# design.net
KiCad netlist of a schematic drawn in Altium Designer
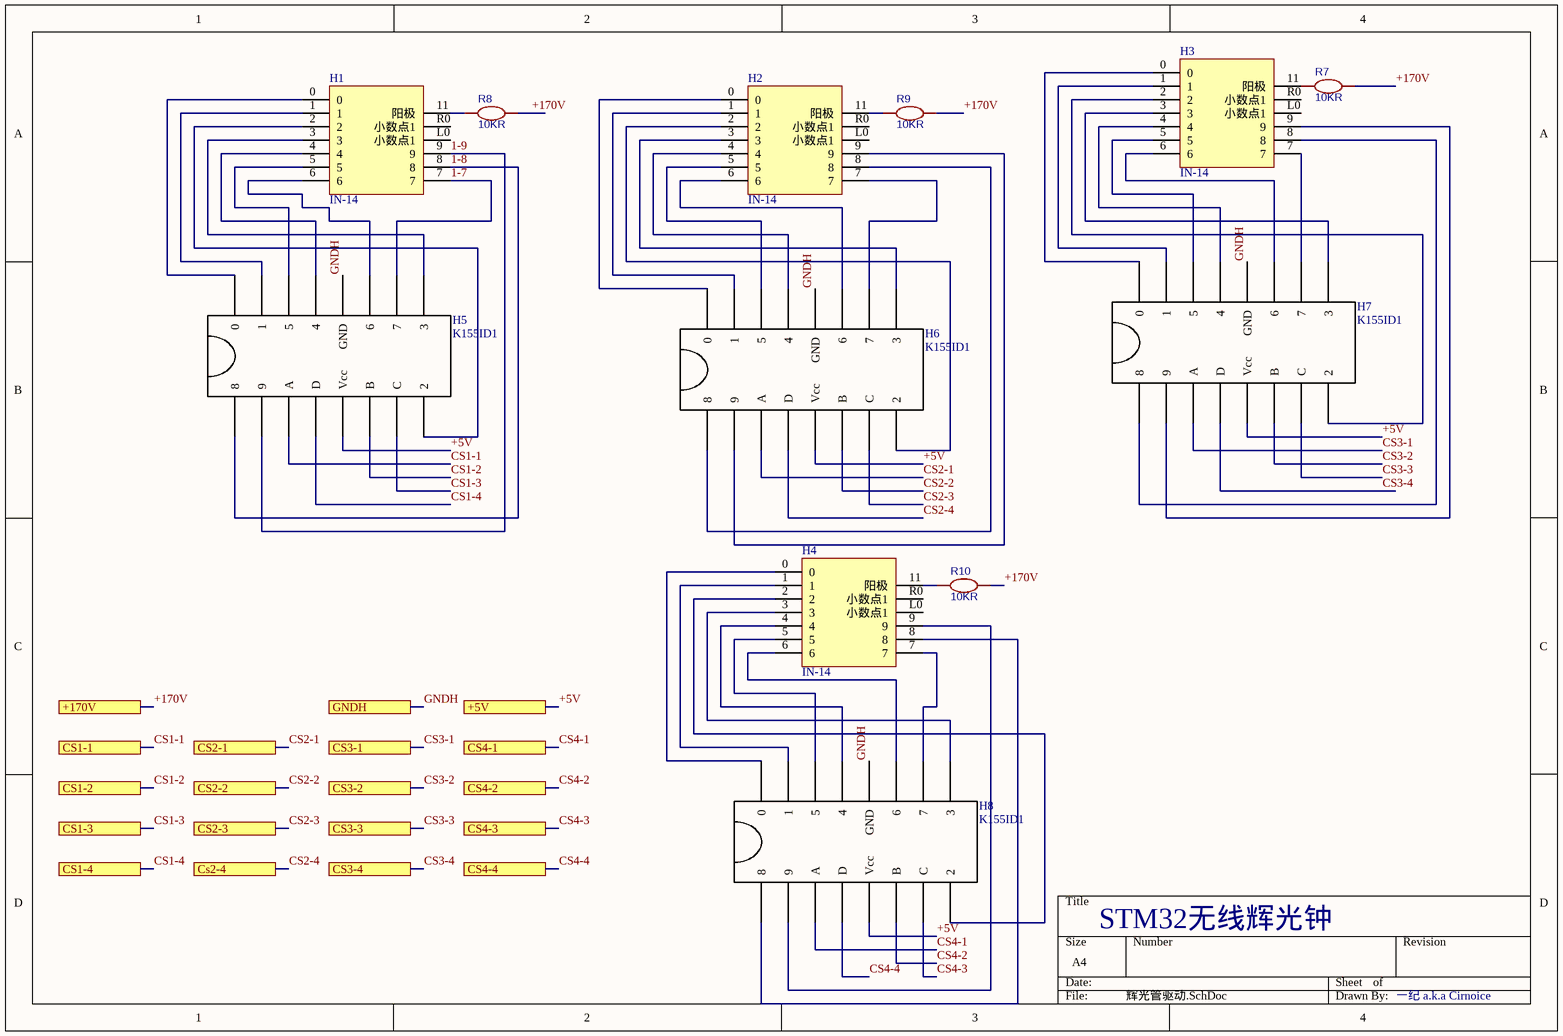
[diagram p0: 辉光管驱动.SchDoc]

(export (version "E")
  (design (tool "Eeschema 10.0.6"))
  (components
    (comp (ref "H1") (value "IN-14") (footprint "IN-14") (libsource (lib "Nixie_ESP32") (part "IN-14")))
    (comp (ref "H2") (value "IN-14") (footprint "IN-14") (libsource (lib "Nixie_ESP32") (part "IN-14")))
    (comp (ref "H3") (value "IN-14") (footprint "IN-14") (libsource (lib "Nixie_ESP32") (part "IN-14")))
    (comp (ref "H4") (value "IN-14") (footprint "IN-14") (libsource (lib "Nixie_ESP32") (part "IN-14")))
    (comp (ref "H5") (value "K155ID1") (footprint "DIP-16") (libsource (lib "Nixie_ESP32") (part "K155ID1")))
    (comp (ref "H6") (value "K155ID1") (footprint "DIP-16") (libsource (lib "Nixie_ESP32") (part "K155ID1")))
    (comp (ref "H7") (value "K155ID1") (footprint "DIP-16") (libsource (lib "Nixie_ESP32") (part "K155ID1")))
    (comp (ref "H8") (value "K155ID1") (footprint "DIP-16") (libsource (lib "Nixie_ESP32") (part "K155ID1")))
    (comp (ref "R7")
      (value "10KR")
      (footprint "R0603")
      (fields (field (name "CONTRIBUTOR") "LCEDA_Lib"))
      (libsource (lib "Nixie_ESP32") (part "0603R"))
    )
    (comp (ref "R8")
      (value "10KR")
      (footprint "R0603")
      (fields (field (name "CONTRIBUTOR") "LCEDA_Lib"))
      (libsource (lib "Nixie_ESP32") (part "0603R"))
    )
    (comp (ref "R9")
      (value "10KR")
      (footprint "R0603")
      (fields (field (name "CONTRIBUTOR") "LCEDA_Lib"))
      (libsource (lib "Nixie_ESP32") (part "0603R"))
    )
    (comp (ref "R10")
      (value "10KR")
      (footprint "R0603")
      (fields (field (name "CONTRIBUTOR") "LCEDA_Lib"))
      (libsource (lib "Nixie_ESP32") (part "0603R"))
    )
  )
  (nets
    (net (code "1") (name "/+5V") (class "Default")
      (node (ref "H5") (pin "5") (pinfunction "Vcc_5") (pintype "passive"))
      (node (ref "H6") (pin "5") (pinfunction "Vcc_5") (pintype "passive"))
      (node (ref "H7") (pin "5") (pinfunction "Vcc_5") (pintype "passive"))
      (node (ref "H8") (pin "5") (pinfunction "Vcc_5") (pintype "passive"))
    )
    (net (code "2") (name "/+170V") (class "Default")
      (node (ref "R10") (pin "2") (pinfunction "2_2") (pintype "passive"))
      (node (ref "R7") (pin "2") (pinfunction "2_2") (pintype "passive"))
      (node (ref "R8") (pin "2") (pinfunction "2_2") (pintype "passive"))
      (node (ref "R9") (pin "2") (pinfunction "2_2") (pintype "passive"))
    )
    (net (code "3") (name "/1-7") (class "Default")
      (node (ref "H1") (pin "7") (pinfunction "7_7") (pintype "passive"))
      (node (ref "H5") (pin "10") (pinfunction "7_10") (pintype "passive"))
    )
    (net (code "4") (name "/1-8") (class "Default")
      (node (ref "H1") (pin "8") (pinfunction "8_8") (pintype "passive"))
      (node (ref "H5") (pin "1") (pinfunction "8_1") (pintype "passive"))
    )
    (net (code "5") (name "/1-9") (class "Default")
      (node (ref "H1") (pin "9") (pinfunction "9_9") (pintype "passive"))
      (node (ref "H5") (pin "2") (pinfunction "9_2") (pintype "passive"))
    )
    (net (code "6") (name "/CS1-1") (class "Default")
      (node (ref "H5") (pin "3") (pinfunction "A_3") (pintype "passive"))
    )
    (net (code "7") (name "/CS1-2") (class "Default")
      (node (ref "H5") (pin "6") (pinfunction "B_6") (pintype "passive"))
    )
    (net (code "8") (name "/CS1-3") (class "Default")
      (node (ref "H5") (pin "7") (pinfunction "C_7") (pintype "passive"))
    )
    (net (code "9") (name "/CS1-4") (class "Default")
      (node (ref "H5") (pin "4") (pinfunction "D_4") (pintype "passive"))
    )
    (net (code "10") (name "/CS2-1") (class "Default")
      (node (ref "H6") (pin "3") (pinfunction "A_3") (pintype "passive"))
    )
    (net (code "11") (name "/CS2-2") (class "Default")
      (node (ref "H6") (pin "6") (pinfunction "B_6") (pintype "passive"))
    )
    (net (code "12") (name "/CS2-3") (class "Default")
      (node (ref "H6") (pin "7") (pinfunction "C_7") (pintype "passive"))
    )
    (net (code "13") (name "/CS2-4") (class "Default")
      (node (ref "H6") (pin "4") (pinfunction "D_4") (pintype "passive"))
    )
    (net (code "14") (name "/CS3-1") (class "Default")
      (node (ref "H7") (pin "3") (pinfunction "A_3") (pintype "passive"))
    )
    (net (code "15") (name "/CS3-2") (class "Default")
      (node (ref "H7") (pin "6") (pinfunction "B_6") (pintype "passive"))
    )
    (net (code "16") (name "/CS3-3") (class "Default")
      (node (ref "H7") (pin "7") (pinfunction "C_7") (pintype "passive"))
    )
    (net (code "17") (name "/CS3-4") (class "Default")
      (node (ref "H7") (pin "4") (pinfunction "D_4") (pintype "passive"))
    )
    (net (code "18") (name "/CS4-1") (class "Default")
      (node (ref "H8") (pin "3") (pinfunction "A_3") (pintype "passive"))
    )
    (net (code "19") (name "/CS4-2") (class "Default")
      (node (ref "H8") (pin "6") (pinfunction "B_6") (pintype "passive"))
    )
    (net (code "20") (name "/CS4-3") (class "Default")
      (node (ref "H8") (pin "7") (pinfunction "C_7") (pintype "passive"))
    )
    (net (code "21") (name "/CS4-4") (class "Default")
      (node (ref "H8") (pin "4") (pinfunction "D_4") (pintype "passive"))
    )
    (net (code "22") (name "/GNDH") (class "Default")
      (node (ref "H5") (pin "12") (pinfunction "GND_12") (pintype "passive"))
      (node (ref "H6") (pin "12") (pinfunction "GND_12") (pintype "passive"))
      (node (ref "H7") (pin "12") (pinfunction "GND_12") (pintype "passive"))
      (node (ref "H8") (pin "12") (pinfunction "GND_12") (pintype "passive"))
    )
    (net (code "23") (name "Net-(H1-阳极)") (class "Default")
      (node (ref "H1") (pin "11") (pinfunction "阳极_11") (pintype "passive"))
      (node (ref "R8") (pin "1") (pinfunction "1_1") (pintype "passive"))
    )
    (net (code "24") (name "Net-(H2-阳极)") (class "Default")
      (node (ref "H2") (pin "11") (pinfunction "阳极_11") (pintype "passive"))
      (node (ref "R9") (pin "1") (pinfunction "1_1") (pintype "passive"))
    )
    (net (code "25") (name "Net-(H3-阳极)") (class "Default")
      (node (ref "H3") (pin "11") (pinfunction "阳极_11") (pintype "passive"))
      (node (ref "R7") (pin "1") (pinfunction "1_1") (pintype "passive"))
    )
    (net (code "26") (name "Net-(H4-阳极)") (class "Default")
      (node (ref "H4") (pin "11") (pinfunction "阳极_11") (pintype "passive"))
      (node (ref "R10") (pin "1") (pinfunction "1_1") (pintype "passive"))
    )
    (net (code "27") (name "Net-(H5-0)") (class "Default")
      (node (ref "H1") (pin "0") (pinfunction "0_0") (pintype "passive"))
      (node (ref "H5") (pin "16") (pinfunction "0_16") (pintype "passive"))
    )
    (net (code "28") (name "Net-(H5-1)") (class "Default")
      (node (ref "H1") (pin "1") (pinfunction "1_1") (pintype "passive"))
      (node (ref "H5") (pin "15") (pinfunction "1_15") (pintype "passive"))
    )
    (net (code "29") (name "Net-(H5-2)") (class "Default")
      (node (ref "H1") (pin "2") (pinfunction "2_2") (pintype "passive"))
      (node (ref "H5") (pin "8") (pinfunction "2_8") (pintype "passive"))
    )
    (net (code "30") (name "Net-(H5-3)") (class "Default")
      (node (ref "H1") (pin "3") (pinfunction "3_3") (pintype "passive"))
      (node (ref "H5") (pin "9") (pinfunction "3_9") (pintype "passive"))
    )
    (net (code "31") (name "Net-(H5-4)") (class "Default")
      (node (ref "H1") (pin "4") (pinfunction "4_4") (pintype "passive"))
      (node (ref "H5") (pin "13") (pinfunction "4_13") (pintype "passive"))
    )
    (net (code "32") (name "Net-(H5-5)") (class "Default")
      (node (ref "H1") (pin "5") (pinfunction "5_5") (pintype "passive"))
      (node (ref "H5") (pin "14") (pinfunction "5_14") (pintype "passive"))
    )
    (net (code "33") (name "Net-(H5-6)") (class "Default")
      (node (ref "H1") (pin "6") (pinfunction "6_6") (pintype "passive"))
      (node (ref "H5") (pin "11") (pinfunction "6_11") (pintype "passive"))
    )
    (net (code "34") (name "Net-(H6-0)") (class "Default")
      (node (ref "H2") (pin "0") (pinfunction "0_0") (pintype "passive"))
      (node (ref "H6") (pin "16") (pinfunction "0_16") (pintype "passive"))
    )
    (net (code "35") (name "Net-(H6-1)") (class "Default")
      (node (ref "H2") (pin "1") (pinfunction "1_1") (pintype "passive"))
      (node (ref "H6") (pin "15") (pinfunction "1_15") (pintype "passive"))
    )
    (net (code "36") (name "Net-(H6-2)") (class "Default")
      (node (ref "H2") (pin "2") (pinfunction "2_2") (pintype "passive"))
      (node (ref "H6") (pin "8") (pinfunction "2_8") (pintype "passive"))
    )
    (net (code "37") (name "Net-(H6-3)") (class "Default")
      (node (ref "H2") (pin "3") (pinfunction "3_3") (pintype "passive"))
      (node (ref "H6") (pin "9") (pinfunction "3_9") (pintype "passive"))
    )
    (net (code "38") (name "Net-(H6-4)") (class "Default")
      (node (ref "H2") (pin "4") (pinfunction "4_4") (pintype "passive"))
      (node (ref "H6") (pin "13") (pinfunction "4_13") (pintype "passive"))
    )
    (net (code "39") (name "Net-(H6-5)") (class "Default")
      (node (ref "H2") (pin "5") (pinfunction "5_5") (pintype "passive"))
      (node (ref "H6") (pin "14") (pinfunction "5_14") (pintype "passive"))
    )
    (net (code "40") (name "Net-(H6-6)") (class "Default")
      (node (ref "H2") (pin "6") (pinfunction "6_6") (pintype "passive"))
      (node (ref "H6") (pin "11") (pinfunction "6_11") (pintype "passive"))
    )
    (net (code "41") (name "Net-(H6-7)") (class "Default")
      (node (ref "H2") (pin "7") (pinfunction "7_7") (pintype "passive"))
      (node (ref "H6") (pin "10") (pinfunction "7_10") (pintype "passive"))
    )
    (net (code "42") (name "Net-(H6-8)") (class "Default")
      (node (ref "H2") (pin "8") (pinfunction "8_8") (pintype "passive"))
      (node (ref "H6") (pin "1") (pinfunction "8_1") (pintype "passive"))
    )
    (net (code "43") (name "Net-(H6-9)") (class "Default")
      (node (ref "H2") (pin "9") (pinfunction "9_9") (pintype "passive"))
      (node (ref "H6") (pin "2") (pinfunction "9_2") (pintype "passive"))
    )
    (net (code "44") (name "Net-(H7-0)") (class "Default")
      (node (ref "H3") (pin "0") (pinfunction "0_0") (pintype "passive"))
      (node (ref "H7") (pin "16") (pinfunction "0_16") (pintype "passive"))
    )
    (net (code "45") (name "Net-(H7-1)") (class "Default")
      (node (ref "H3") (pin "1") (pinfunction "1_1") (pintype "passive"))
      (node (ref "H7") (pin "15") (pinfunction "1_15") (pintype "passive"))
    )
    (net (code "46") (name "Net-(H7-2)") (class "Default")
      (node (ref "H3") (pin "2") (pinfunction "2_2") (pintype "passive"))
      (node (ref "H7") (pin "8") (pinfunction "2_8") (pintype "passive"))
    )
    (net (code "47") (name "Net-(H7-3)") (class "Default")
      (node (ref "H3") (pin "3") (pinfunction "3_3") (pintype "passive"))
      (node (ref "H7") (pin "9") (pinfunction "3_9") (pintype "passive"))
    )
    (net (code "48") (name "Net-(H7-4)") (class "Default")
      (node (ref "H3") (pin "4") (pinfunction "4_4") (pintype "passive"))
      (node (ref "H7") (pin "13") (pinfunction "4_13") (pintype "passive"))
    )
    (net (code "49") (name "Net-(H7-5)") (class "Default")
      (node (ref "H3") (pin "5") (pinfunction "5_5") (pintype "passive"))
      (node (ref "H7") (pin "14") (pinfunction "5_14") (pintype "passive"))
    )
    (net (code "50") (name "Net-(H7-6)") (class "Default")
      (node (ref "H3") (pin "6") (pinfunction "6_6") (pintype "passive"))
      (node (ref "H7") (pin "11") (pinfunction "6_11") (pintype "passive"))
    )
    (net (code "51") (name "Net-(H7-7)") (class "Default")
      (node (ref "H3") (pin "7") (pinfunction "7_7") (pintype "passive"))
      (node (ref "H7") (pin "10") (pinfunction "7_10") (pintype "passive"))
    )
    (net (code "52") (name "Net-(H7-8)") (class "Default")
      (node (ref "H3") (pin "8") (pinfunction "8_8") (pintype "passive"))
      (node (ref "H7") (pin "1") (pinfunction "8_1") (pintype "passive"))
    )
    (net (code "53") (name "Net-(H7-9)") (class "Default")
      (node (ref "H3") (pin "9") (pinfunction "9_9") (pintype "passive"))
      (node (ref "H7") (pin "2") (pinfunction "9_2") (pintype "passive"))
    )
    (net (code "54") (name "Net-(H8-0)") (class "Default")
      (node (ref "H4") (pin "0") (pinfunction "0_0") (pintype "passive"))
      (node (ref "H8") (pin "16") (pinfunction "0_16") (pintype "passive"))
    )
    (net (code "55") (name "Net-(H8-1)") (class "Default")
      (node (ref "H4") (pin "1") (pinfunction "1_1") (pintype "passive"))
      (node (ref "H8") (pin "15") (pinfunction "1_15") (pintype "passive"))
    )
    (net (code "56") (name "Net-(H8-2)") (class "Default")
      (node (ref "H4") (pin "2") (pinfunction "2_2") (pintype "passive"))
      (node (ref "H8") (pin "8") (pinfunction "2_8") (pintype "passive"))
    )
    (net (code "57") (name "Net-(H8-3)") (class "Default")
      (node (ref "H4") (pin "3") (pinfunction "3_3") (pintype "passive"))
      (node (ref "H8") (pin "9") (pinfunction "3_9") (pintype "passive"))
    )
    (net (code "58") (name "Net-(H8-4)") (class "Default")
      (node (ref "H4") (pin "4") (pinfunction "4_4") (pintype "passive"))
      (node (ref "H8") (pin "13") (pinfunction "4_13") (pintype "passive"))
    )
    (net (code "59") (name "Net-(H8-5)") (class "Default")
      (node (ref "H4") (pin "5") (pinfunction "5_5") (pintype "passive"))
      (node (ref "H8") (pin "14") (pinfunction "5_14") (pintype "passive"))
    )
    (net (code "60") (name "Net-(H8-6)") (class "Default")
      (node (ref "H4") (pin "6") (pinfunction "6_6") (pintype "passive"))
      (node (ref "H8") (pin "11") (pinfunction "6_11") (pintype "passive"))
    )
    (net (code "61") (name "Net-(H8-7)") (class "Default")
      (node (ref "H4") (pin "7") (pinfunction "7_7") (pintype "passive"))
      (node (ref "H8") (pin "10") (pinfunction "7_10") (pintype "passive"))
    )
    (net (code "62") (name "Net-(H8-8)") (class "Default")
      (node (ref "H4") (pin "8") (pinfunction "8_8") (pintype "passive"))
      (node (ref "H8") (pin "1") (pinfunction "8_1") (pintype "passive"))
    )
    (net (code "63") (name "Net-(H8-9)") (class "Default")
      (node (ref "H4") (pin "9") (pinfunction "9_9") (pintype "passive"))
      (node (ref "H8") (pin "2") (pinfunction "9_2") (pintype "passive"))
    )
    (net (code "64") (name "unconnected-(H1-小数点1-PadL0)") (class "Default")
      (node (ref "H1") (pin "L0") (pinfunction "小数点1_L0") (pintype "passive"))
    )
    (net (code "65") (name "unconnected-(H1-小数点1-PadR0)") (class "Default")
      (node (ref "H1") (pin "R0") (pinfunction "小数点1_R0") (pintype "passive"))
    )
    (net (code "66") (name "unconnected-(H2-小数点1-PadL0)") (class "Default")
      (node (ref "H2") (pin "L0") (pinfunction "小数点1_L0") (pintype "passive"))
    )
    (net (code "67") (name "unconnected-(H2-小数点1-PadR0)") (class "Default")
      (node (ref "H2") (pin "R0") (pinfunction "小数点1_R0") (pintype "passive"))
    )
    (net (code "68") (name "unconnected-(H3-小数点1-PadL0)") (class "Default")
      (node (ref "H3") (pin "L0") (pinfunction "小数点1_L0") (pintype "passive"))
    )
    (net (code "69") (name "unconnected-(H3-小数点1-PadR0)") (class "Default")
      (node (ref "H3") (pin "R0") (pinfunction "小数点1_R0") (pintype "passive"))
    )
    (net (code "70") (name "unconnected-(H4-小数点1-PadL0)") (class "Default")
      (node (ref "H4") (pin "L0") (pinfunction "小数点1_L0") (pintype "passive"))
    )
    (net (code "71") (name "unconnected-(H4-小数点1-PadR0)") (class "Default")
      (node (ref "H4") (pin "R0") (pinfunction "小数点1_R0") (pintype "passive"))
    )
  )
)
